# 6_DIG.net
KiCad netlist of a schematic drawn in Altium Designer
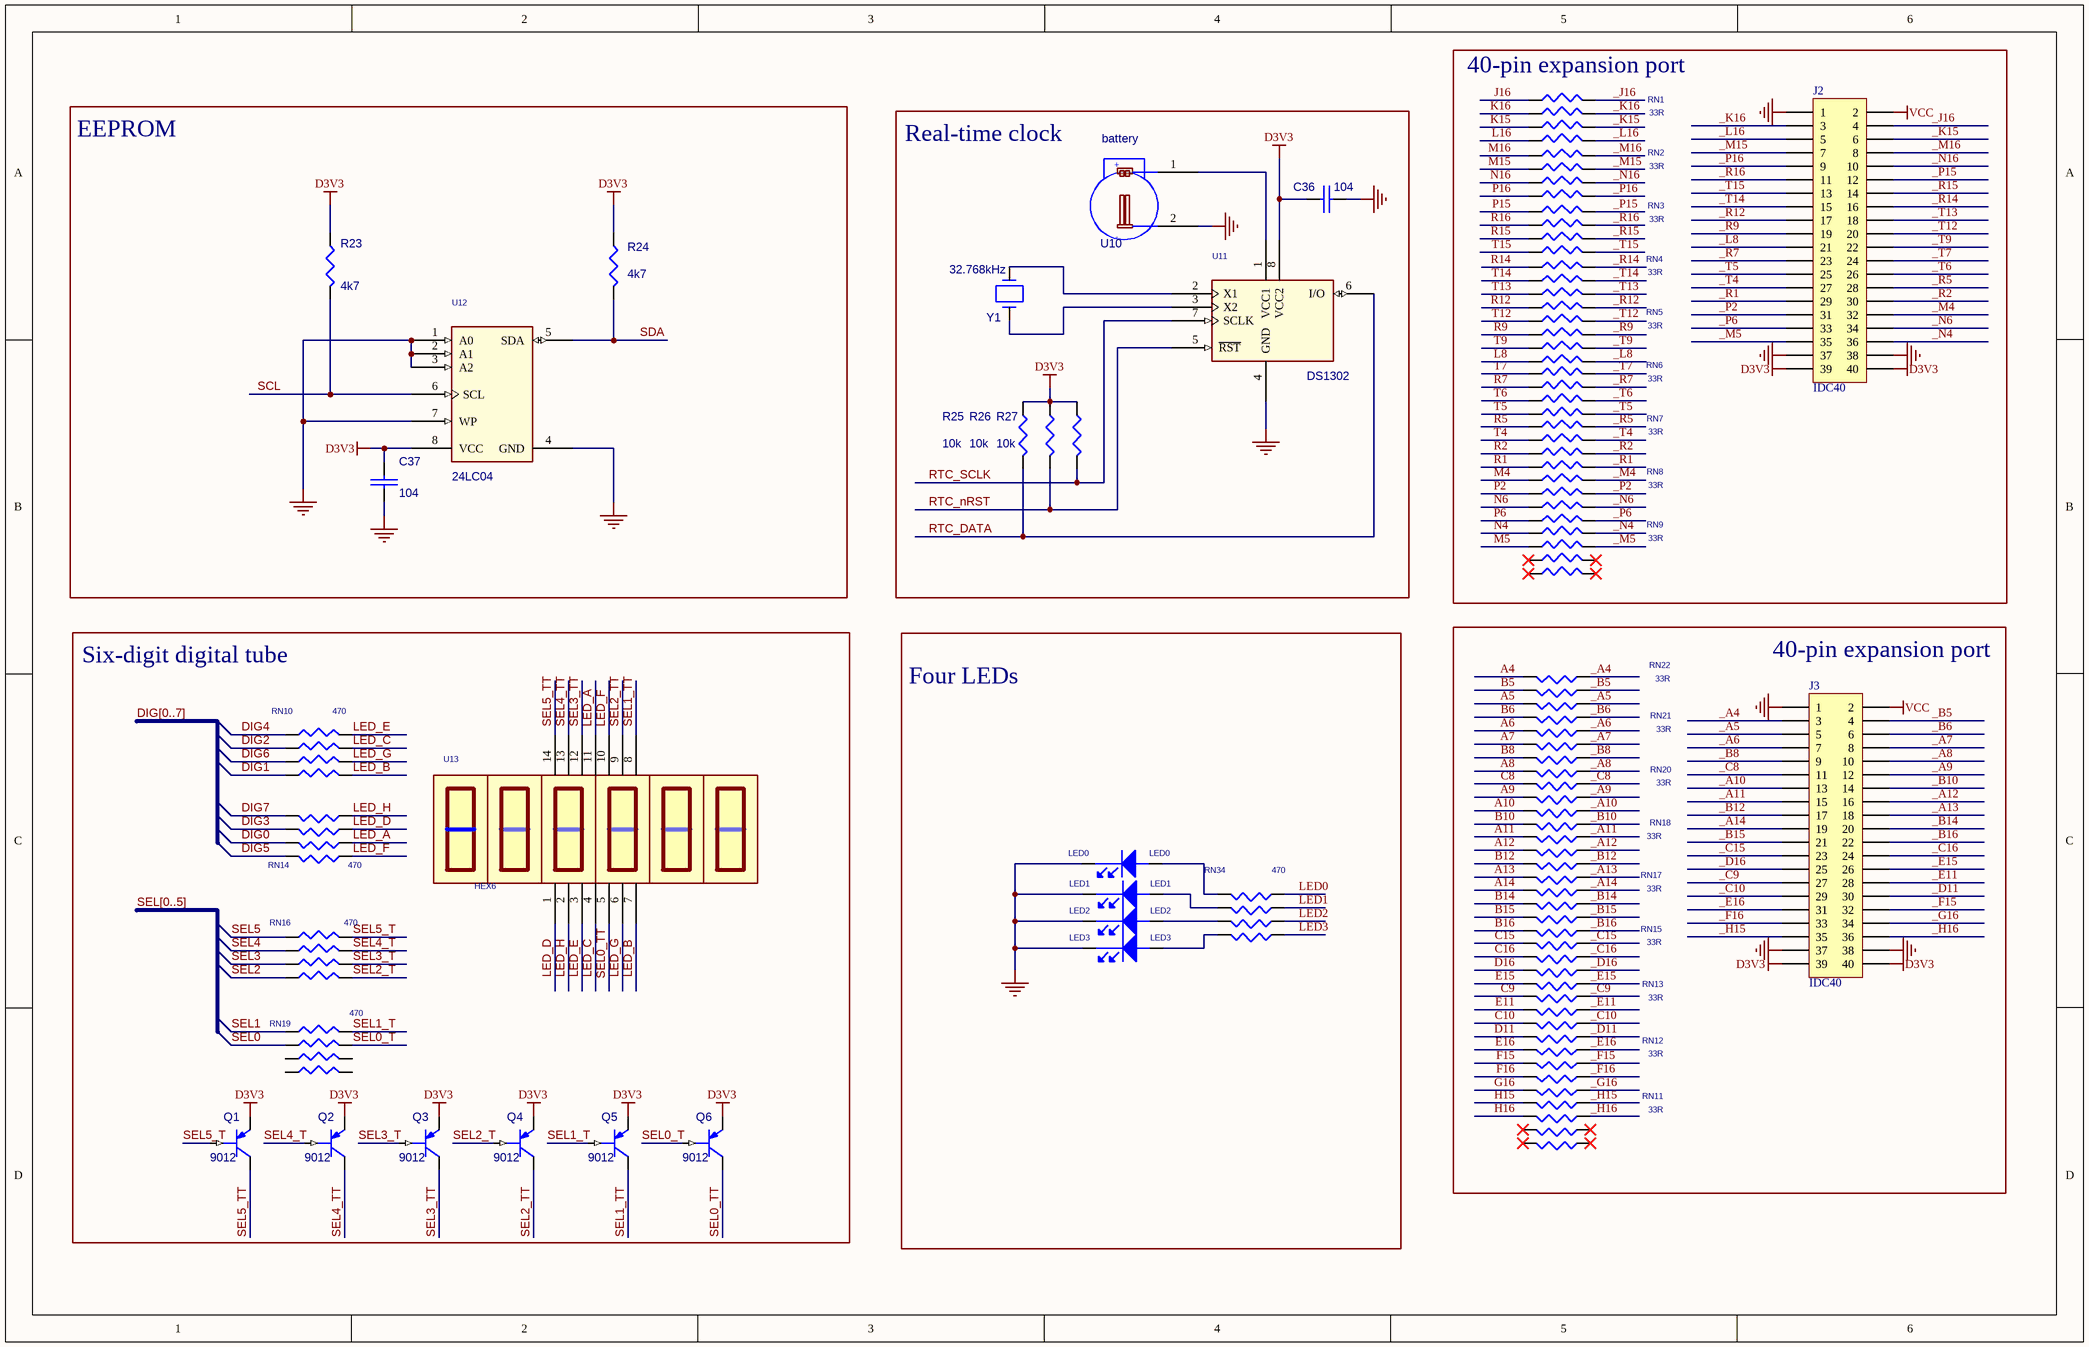
[diagram p0: 6_DIG.SchDoc]

(export (version "E")
  (design (tool "Eeschema 10.0.6"))
  (components
    (comp (ref "C36") (value "104") (footprint "0402") (libsource (lib "*") (part "C_Dup3")))
    (comp (ref "C37") (value "104") (footprint "0402") (libsource (lib "*") (part "C_Dup4")))
    (comp (ref "J2")
      (value "IDC40")
      (footprint "IDC-40J")
      (description "Header, 20-Pin, Dual row")
      (fields (field (name "PUBLISHER") "Altium Limited"))
      (libsource (lib "Miscellaneous Connectors") (part "MHDR2X20"))
    )
    (comp (ref "J3")
      (value "IDC40")
      (footprint "IDC-40J")
      (description "Header, 20-Pin, Dual row")
      (fields (field (name "PUBLISHER") "Altium Limited"))
      (libsource (lib "Miscellaneous Connectors") (part "MHDR2X20"))
    )
    (comp (ref "LED0") (value "LED0") (footprint "LEDSO") (libsource (lib "*") (part "LED_Dup1")))
    (comp (ref "LED1") (value "LED1") (footprint "LEDso") (libsource (lib "*") (part "LED_Dup1")))
    (comp (ref "LED2") (value "LED2") (footprint "LEDSO") (libsource (lib "*") (part "LED_Dup1")))
    (comp (ref "LED3") (value "LED3") (footprint "LEDSO") (libsource (lib "*") (part "LED_Dup1")))
    (comp (ref "Q1") (value "9012") (footprint "SOT23") (libsource (lib "*") (part "PNP")))
    (comp (ref "Q2") (value "9012") (footprint "SOT23") (libsource (lib "*") (part "PNP")))
    (comp (ref "Q3") (value "9012") (footprint "SOT23") (libsource (lib "*") (part "PNP")))
    (comp (ref "Q4") (value "9012") (footprint "SOT23") (libsource (lib "*") (part "PNP")))
    (comp (ref "Q5") (value "9012") (footprint "SOT23") (libsource (lib "*") (part "PNP")))
    (comp (ref "Q6") (value "9012") (footprint "SOT23") (libsource (lib "*") (part "PNP")))
    (comp (ref "R23") (value "4k7") (footprint "0603") (libsource (lib "*") (part "R_Dup6")))
    (comp (ref "R24") (value "4k7") (footprint "0603") (libsource (lib "*") (part "R_Dup6")))
    (comp (ref "R25") (value "10k") (footprint "0603") (libsource (lib "*") (part "R_Dup5")))
    (comp (ref "R26") (value "10k") (footprint "0603") (libsource (lib "*") (part "R_Dup5")))
    (comp (ref "R27") (value "10k") (footprint "0603") (libsource (lib "*") (part "R_Dup5")))
    (comp (ref "RN1") (value "33R") (footprint "RN-8P") (libsource (lib "*") (part "RN_Dup1")))
    (comp (ref "RN2") (value "33R") (footprint "RN-8P") (libsource (lib "*") (part "RN_Dup1")))
    (comp (ref "RN3") (value "33R") (footprint "RN-8P") (libsource (lib "*") (part "RN_Dup1")))
    (comp (ref "RN4") (value "33R") (footprint "RN-8P") (libsource (lib "*") (part "RN_Dup1")))
    (comp (ref "RN5") (value "33R") (footprint "RN-8P") (libsource (lib "*") (part "RN_Dup1")))
    (comp (ref "RN6") (value "33R") (footprint "RN-8P") (libsource (lib "*") (part "RN_Dup1")))
    (comp (ref "RN7") (value "33R") (footprint "RN-8P") (libsource (lib "*") (part "RN_Dup1")))
    (comp (ref "RN8") (value "33R") (footprint "RN-8P") (libsource (lib "*") (part "RN_Dup1")))
    (comp (ref "RN9") (value "33R") (footprint "RN-8P") (libsource (lib "*") (part "RN_Dup1")))
    (comp (ref "RN10") (value "470") (footprint "RN-8P") (libsource (lib "*") (part "RN")))
    (comp (ref "RN11") (value "33R") (footprint "RN-8P") (libsource (lib "*") (part "RN_Dup1")))
    (comp (ref "RN12") (value "33R") (footprint "RN-8P") (libsource (lib "*") (part "RN_Dup1")))
    (comp (ref "RN13") (value "33R") (footprint "RN-8P") (libsource (lib "*") (part "RN_Dup1")))
    (comp (ref "RN14") (value "470") (footprint "RN-8P") (libsource (lib "*") (part "RN")))
    (comp (ref "RN15") (value "33R") (footprint "RN-8P") (libsource (lib "*") (part "RN_Dup1")))
    (comp (ref "RN16") (value "470") (footprint "RN-8P") (libsource (lib "*") (part "RN")))
    (comp (ref "RN17") (value "33R") (footprint "RN-8P") (libsource (lib "*") (part "RN_Dup1")))
    (comp (ref "RN18") (value "33R") (footprint "RN-8P") (libsource (lib "*") (part "RN_Dup1")))
    (comp (ref "RN19") (value "470") (footprint "RN-8P") (libsource (lib "*") (part "RN")))
    (comp (ref "RN20") (value "33R") (footprint "RN-8P") (libsource (lib "*") (part "RN_Dup1")))
    (comp (ref "RN21") (value "33R") (footprint "RN-8P") (libsource (lib "*") (part "RN_Dup1")))
    (comp (ref "RN22") (value "33R") (footprint "RN-8P") (libsource (lib "*") (part "RN_Dup1")))
    (comp (ref "RN34") (value "470") (footprint "RN-8P") (libsource (lib "*") (part "RN")))
    (comp (ref "U10") (value "battery") (footprint "BATSO") (libsource (lib "*") (part "battery")))
    (comp (ref "U11")
      (value "DS1302")
      (fields (field (name "PART NUMBER") "TMP-13") (field (name "ICA_PARTNUM") "$$2098133$$DS1302S"))
      (libsource (lib "*") (part "DS1302_8SO"))
    )
    (comp (ref "U12") (value "24LC04") (libsource (lib "*") (part "24LC04B_0")))
    (comp (ref "U13") (value "HEX6") (libsource (lib "*") (part "HEX6")))
    (comp (ref "Y1") (value "32.768kHz") (libsource (lib "*") (part "ZTA")))
  )
  (nets
    (net (code "1") (name "/A4") (class "Default")
      (node (ref "RN22") (pin "5") (pinfunction "5_5") (pintype "passive"))
    )
    (net (code "2") (name "/A5") (class "Default")
      (node (ref "RN22") (pin "7") (pinfunction "7_7") (pintype "passive"))
    )
    (net (code "3") (name "/A6") (class "Default")
      (node (ref "RN21") (pin "5") (pinfunction "5_5") (pintype "passive"))
    )
    (net (code "4") (name "/A7") (class "Default")
      (node (ref "RN21") (pin "6") (pinfunction "6_6") (pintype "passive"))
    )
    (net (code "5") (name "/A8") (class "Default")
      (node (ref "RN21") (pin "8") (pinfunction "8_8") (pintype "passive"))
    )
    (net (code "6") (name "/A9") (class "Default")
      (node (ref "RN20") (pin "6") (pinfunction "6_6") (pintype "passive"))
    )
    (net (code "7") (name "/A10") (class "Default")
      (node (ref "RN20") (pin "7") (pinfunction "7_7") (pintype "passive"))
    )
    (net (code "8") (name "/A11") (class "Default")
      (node (ref "RN18") (pin "5") (pinfunction "5_5") (pintype "passive"))
    )
    (net (code "9") (name "/A12") (class "Default")
      (node (ref "RN18") (pin "6") (pinfunction "6_6") (pintype "passive"))
    )
    (net (code "10") (name "/A13") (class "Default")
      (node (ref "RN18") (pin "8") (pinfunction "8_8") (pintype "passive"))
    )
    (net (code "11") (name "/A14") (class "Default")
      (node (ref "RN17") (pin "5") (pinfunction "5_5") (pintype "passive"))
    )
    (net (code "12") (name "/B5") (class "Default")
      (node (ref "RN22") (pin "6") (pinfunction "6_6") (pintype "passive"))
    )
    (net (code "13") (name "/B6") (class "Default")
      (node (ref "RN22") (pin "8") (pinfunction "8_8") (pintype "passive"))
    )
    (net (code "14") (name "/B8") (class "Default")
      (node (ref "RN21") (pin "7") (pinfunction "7_7") (pintype "passive"))
    )
    (net (code "15") (name "/B10") (class "Default")
      (node (ref "RN20") (pin "8") (pinfunction "8_8") (pintype "passive"))
    )
    (net (code "16") (name "/B12") (class "Default")
      (node (ref "RN18") (pin "7") (pinfunction "7_7") (pintype "passive"))
    )
    (net (code "17") (name "/B14") (class "Default")
      (node (ref "RN17") (pin "6") (pinfunction "6_6") (pintype "passive"))
    )
    (net (code "18") (name "/B15") (class "Default")
      (node (ref "RN17") (pin "7") (pinfunction "7_7") (pintype "passive"))
    )
    (net (code "19") (name "/B16") (class "Default")
      (node (ref "RN17") (pin "8") (pinfunction "8_8") (pintype "passive"))
    )
    (net (code "20") (name "/C8") (class "Default")
      (node (ref "RN20") (pin "5") (pinfunction "5_5") (pintype "passive"))
    )
    (net (code "21") (name "/C9") (class "Default")
      (node (ref "RN13") (pin "5") (pinfunction "5_5") (pintype "passive"))
    )
    (net (code "22") (name "/C10") (class "Default")
      (node (ref "RN13") (pin "7") (pinfunction "7_7") (pintype "passive"))
    )
    (net (code "23") (name "/C15") (class "Default")
      (node (ref "RN15") (pin "5") (pinfunction "5_5") (pintype "passive"))
    )
    (net (code "24") (name "/C16") (class "Default")
      (node (ref "RN15") (pin "6") (pinfunction "6_6") (pintype "passive"))
    )
    (net (code "25") (name "/D11") (class "Default")
      (node (ref "RN13") (pin "8") (pinfunction "8_8") (pintype "passive"))
    )
    (net (code "26") (name "/D16") (class "Default")
      (node (ref "RN15") (pin "7") (pinfunction "7_7") (pintype "passive"))
    )
    (net (code "27") (name "/DIG0") (class "Default")
      (node (ref "RN14") (pin "7") (pinfunction "7_7") (pintype "passive"))
    )
    (net (code "28") (name "/DIG1") (class "Default")
      (node (ref "RN10") (pin "5") (pinfunction "5_5") (pintype "passive"))
    )
    (net (code "29") (name "/DIG2") (class "Default")
      (node (ref "RN10") (pin "7") (pinfunction "7_7") (pintype "passive"))
    )
    (net (code "30") (name "/DIG3") (class "Default")
      (node (ref "RN14") (pin "6") (pinfunction "6_6") (pintype "passive"))
    )
    (net (code "31") (name "/DIG4") (class "Default")
      (node (ref "RN10") (pin "8") (pinfunction "8_8") (pintype "passive"))
    )
    (net (code "32") (name "/DIG5") (class "Default")
      (node (ref "RN14") (pin "8") (pinfunction "8_8") (pintype "passive"))
    )
    (net (code "33") (name "/DIG6") (class "Default")
      (node (ref "RN10") (pin "6") (pinfunction "6_6") (pintype "passive"))
    )
    (net (code "34") (name "/DIG7") (class "Default")
      (node (ref "RN14") (pin "5") (pinfunction "5_5") (pintype "passive"))
    )
    (net (code "36") (name "/E11") (class "Default")
      (node (ref "RN13") (pin "6") (pinfunction "6_6") (pintype "passive"))
    )
    (net (code "37") (name "/E15") (class "Default")
      (node (ref "RN15") (pin "8") (pinfunction "8_8") (pintype "passive"))
    )
    (net (code "38") (name "/E16") (class "Default")
      (node (ref "RN12") (pin "5") (pinfunction "5_5") (pintype "passive"))
    )
    (net (code "39") (name "/F15") (class "Default")
      (node (ref "RN12") (pin "6") (pinfunction "6_6") (pintype "passive"))
    )
    (net (code "40") (name "/F16") (class "Default")
      (node (ref "RN12") (pin "7") (pinfunction "7_7") (pintype "passive"))
    )
    (net (code "41") (name "/G16") (class "Default")
      (node (ref "RN12") (pin "8") (pinfunction "8_8") (pintype "passive"))
    )
    (net (code "42") (name "/H15") (class "Default")
      (node (ref "RN11") (pin "5") (pinfunction "5_5") (pintype "passive"))
    )
    (net (code "43") (name "/H16") (class "Default")
      (node (ref "RN11") (pin "6") (pinfunction "6_6") (pintype "passive"))
    )
    (net (code "44") (name "/J16") (class "Default")
      (node (ref "RN1") (pin "1") (pinfunction "1_1") (pintype "passive"))
    )
    (net (code "45") (name "/K15") (class "Default")
      (node (ref "RN1") (pin "3") (pinfunction "3_3") (pintype "passive"))
    )
    (net (code "46") (name "/K16") (class "Default")
      (node (ref "RN1") (pin "2") (pinfunction "2_2") (pintype "passive"))
    )
    (net (code "47") (name "/L8") (class "Default")
      (node (ref "RN5") (pin "4") (pinfunction "4_4") (pintype "passive"))
    )
    (net (code "48") (name "/L16") (class "Default")
      (node (ref "RN1") (pin "4") (pinfunction "4_4") (pintype "passive"))
    )
    (net (code "49") (name "/LED0") (class "Default")
      (node (ref "RN34") (pin "4") (pinfunction "4_4") (pintype "passive"))
    )
    (net (code "50") (name "/LED1") (class "Default")
      (node (ref "RN34") (pin "3") (pinfunction "3_3") (pintype "passive"))
    )
    (net (code "51") (name "/LED2") (class "Default")
      (node (ref "RN34") (pin "2") (pinfunction "2_2") (pintype "passive"))
    )
    (net (code "52") (name "/LED3") (class "Default")
      (node (ref "RN34") (pin "1") (pinfunction "1_1") (pintype "passive"))
    )
    (net (code "53") (name "/LED_A") (class "Default")
      (node (ref "RN14") (pin "2") (pinfunction "2_2") (pintype "passive"))
      (node (ref "U13") (pin "11") (pinfunction "11_11") (pintype "passive"))
    )
    (net (code "54") (name "/LED_B") (class "Default")
      (node (ref "RN10") (pin "4") (pinfunction "4_4") (pintype "passive"))
      (node (ref "U13") (pin "7") (pinfunction "7_7") (pintype "passive"))
    )
    (net (code "55") (name "/LED_C") (class "Default")
      (node (ref "RN10") (pin "2") (pinfunction "2_2") (pintype "passive"))
      (node (ref "U13") (pin "4") (pinfunction "4_4") (pintype "passive"))
    )
    (net (code "56") (name "/LED_D") (class "Default")
      (node (ref "RN14") (pin "3") (pinfunction "3_3") (pintype "passive"))
      (node (ref "U13") (pin "1") (pinfunction "1_1") (pintype "passive"))
    )
    (net (code "57") (name "/LED_E") (class "Default")
      (node (ref "RN10") (pin "1") (pinfunction "1_1") (pintype "passive"))
      (node (ref "U13") (pin "3") (pinfunction "3_3") (pintype "passive"))
    )
    (net (code "58") (name "/LED_F") (class "Default")
      (node (ref "RN14") (pin "1") (pinfunction "1_1") (pintype "passive"))
      (node (ref "U13") (pin "10") (pinfunction "10_10") (pintype "passive"))
    )
    (net (code "59") (name "/LED_G") (class "Default")
      (node (ref "RN10") (pin "3") (pinfunction "3_3") (pintype "passive"))
      (node (ref "U13") (pin "6") (pinfunction "6_6") (pintype "passive"))
    )
    (net (code "60") (name "/LED_H") (class "Default")
      (node (ref "RN14") (pin "4") (pinfunction "4_4") (pintype "passive"))
      (node (ref "U13") (pin "2") (pinfunction "2_2") (pintype "passive"))
    )
    (net (code "61") (name "/M4") (class "Default")
      (node (ref "RN8") (pin "1") (pinfunction "1_1") (pintype "passive"))
    )
    (net (code "62") (name "/M5") (class "Default")
      (node (ref "RN9") (pin "2") (pinfunction "2_2") (pintype "passive"))
    )
    (net (code "63") (name "/M15") (class "Default")
      (node (ref "RN2") (pin "2") (pinfunction "2_2") (pintype "passive"))
    )
    (net (code "64") (name "/M16") (class "Default")
      (node (ref "RN2") (pin "1") (pinfunction "1_1") (pintype "passive"))
    )
    (net (code "65") (name "/N4") (class "Default")
      (node (ref "RN9") (pin "1") (pinfunction "1_1") (pintype "passive"))
    )
    (net (code "66") (name "/N6") (class "Default")
      (node (ref "RN8") (pin "3") (pinfunction "3_3") (pintype "passive"))
    )
    (net (code "67") (name "/N16") (class "Default")
      (node (ref "RN2") (pin "3") (pinfunction "3_3") (pintype "passive"))
    )
    (net (code "68") (name "/P2") (class "Default")
      (node (ref "RN8") (pin "2") (pinfunction "2_2") (pintype "passive"))
    )
    (net (code "69") (name "/P6") (class "Default")
      (node (ref "RN8") (pin "4") (pinfunction "4_4") (pintype "passive"))
    )
    (net (code "70") (name "/P15") (class "Default")
      (node (ref "RN3") (pin "1") (pinfunction "1_1") (pintype "passive"))
    )
    (net (code "71") (name "/P16") (class "Default")
      (node (ref "RN2") (pin "4") (pinfunction "4_4") (pintype "passive"))
    )
    (net (code "72") (name "/R1") (class "Default")
      (node (ref "RN7") (pin "4") (pinfunction "4_4") (pintype "passive"))
    )
    (net (code "73") (name "/R2") (class "Default")
      (node (ref "RN7") (pin "3") (pinfunction "3_3") (pintype "passive"))
    )
    (net (code "74") (name "/R5") (class "Default")
      (node (ref "RN7") (pin "1") (pinfunction "1_1") (pintype "passive"))
    )
    (net (code "75") (name "/R7") (class "Default")
      (node (ref "RN6") (pin "2") (pinfunction "2_2") (pintype "passive"))
    )
    (net (code "76") (name "/R9") (class "Default")
      (node (ref "RN5") (pin "2") (pinfunction "2_2") (pintype "passive"))
    )
    (net (code "77") (name "/R12") (class "Default")
      (node (ref "RN4") (pin "4") (pinfunction "4_4") (pintype "passive"))
    )
    (net (code "78") (name "/R14") (class "Default")
      (node (ref "RN4") (pin "1") (pinfunction "1_1") (pintype "passive"))
    )
    (net (code "79") (name "/R15") (class "Default")
      (node (ref "RN3") (pin "3") (pinfunction "3_3") (pintype "passive"))
    )
    (net (code "80") (name "/R16") (class "Default")
      (node (ref "RN3") (pin "2") (pinfunction "2_2") (pintype "passive"))
    )
    (net (code "81") (name "/RTC_DATA") (class "Default")
      (node (ref "R25") (pin "2") (pinfunction "2_2") (pintype "passive"))
      (node (ref "U11") (pin "6") (pinfunction "I/O_6") (pintype "bidirectional"))
    )
    (net (code "82") (name "/RTC_SCLK") (class "Default")
      (node (ref "R27") (pin "2") (pinfunction "2_2") (pintype "passive"))
      (node (ref "U11") (pin "7") (pinfunction "SCLK_7") (pintype "input"))
    )
    (net (code "83") (name "/RTC_nRST") (class "Default")
      (node (ref "R26") (pin "2") (pinfunction "2_2") (pintype "passive"))
      (node (ref "U11") (pin "5") (pinfunction "~{RST}_5") (pintype "input"))
    )
    (net (code "84") (name "/SCL") (class "Default")
      (node (ref "R23") (pin "2") (pinfunction "2_2") (pintype "passive"))
      (node (ref "U12") (pin "6") (pinfunction "SCL_6") (pintype "input"))
    )
    (net (code "85") (name "/SDA") (class "Default")
      (node (ref "R24") (pin "2") (pinfunction "2_2") (pintype "passive"))
      (node (ref "U12") (pin "5") (pinfunction "SDA_5") (pintype "bidirectional"))
    )
    (net (code "86") (name "/SEL0") (class "Default")
      (node (ref "RN19") (pin "7") (pinfunction "7_7") (pintype "passive"))
    )
    (net (code "87") (name "/SEL0_T") (class "Default")
      (node (ref "Q6") (pin "1") (pinfunction "BASE_1") (pintype "input"))
      (node (ref "RN19") (pin "2") (pinfunction "2_2") (pintype "passive"))
    )
    (net (code "88") (name "/SEL0_TT") (class "Default")
      (node (ref "Q6") (pin "3") (pinfunction "COLLECTOR_3") (pintype "passive"))
      (node (ref "U13") (pin "5") (pinfunction "5_5") (pintype "passive"))
    )
    (net (code "89") (name "/SEL1") (class "Default")
      (node (ref "RN19") (pin "8") (pinfunction "8_8") (pintype "passive"))
    )
    (net (code "90") (name "/SEL1_T") (class "Default")
      (node (ref "Q5") (pin "1") (pinfunction "BASE_1") (pintype "input"))
      (node (ref "RN19") (pin "1") (pinfunction "1_1") (pintype "passive"))
    )
    (net (code "91") (name "/SEL1_TT") (class "Default")
      (node (ref "Q5") (pin "3") (pinfunction "COLLECTOR_3") (pintype "passive"))
      (node (ref "U13") (pin "8") (pinfunction "8_8") (pintype "passive"))
    )
    (net (code "92") (name "/SEL2") (class "Default")
      (node (ref "RN16") (pin "5") (pinfunction "5_5") (pintype "passive"))
    )
    (net (code "93") (name "/SEL2_T") (class "Default")
      (node (ref "Q4") (pin "1") (pinfunction "BASE_1") (pintype "input"))
      (node (ref "RN16") (pin "4") (pinfunction "4_4") (pintype "passive"))
    )
    (net (code "94") (name "/SEL2_TT") (class "Default")
      (node (ref "Q4") (pin "3") (pinfunction "COLLECTOR_3") (pintype "passive"))
      (node (ref "U13") (pin "9") (pinfunction "9_9") (pintype "passive"))
    )
    (net (code "95") (name "/SEL3") (class "Default")
      (node (ref "RN16") (pin "6") (pinfunction "6_6") (pintype "passive"))
    )
    (net (code "96") (name "/SEL3_T") (class "Default")
      (node (ref "Q3") (pin "1") (pinfunction "BASE_1") (pintype "input"))
      (node (ref "RN16") (pin "3") (pinfunction "3_3") (pintype "passive"))
    )
    (net (code "97") (name "/SEL3_TT") (class "Default")
      (node (ref "Q3") (pin "3") (pinfunction "COLLECTOR_3") (pintype "passive"))
      (node (ref "U13") (pin "12") (pinfunction "12_12") (pintype "passive"))
    )
    (net (code "98") (name "/SEL4") (class "Default")
      (node (ref "RN16") (pin "7") (pinfunction "7_7") (pintype "passive"))
    )
    (net (code "99") (name "/SEL4_T") (class "Default")
      (node (ref "Q2") (pin "1") (pinfunction "BASE_1") (pintype "input"))
      (node (ref "RN16") (pin "2") (pinfunction "2_2") (pintype "passive"))
    )
    (net (code "100") (name "/SEL4_TT") (class "Default")
      (node (ref "Q2") (pin "3") (pinfunction "COLLECTOR_3") (pintype "passive"))
      (node (ref "U13") (pin "13") (pinfunction "13_13") (pintype "passive"))
    )
    (net (code "101") (name "/SEL5") (class "Default")
      (node (ref "RN16") (pin "8") (pinfunction "8_8") (pintype "passive"))
    )
    (net (code "102") (name "/SEL5_T") (class "Default")
      (node (ref "Q1") (pin "1") (pinfunction "BASE_1") (pintype "input"))
      (node (ref "RN16") (pin "1") (pinfunction "1_1") (pintype "passive"))
    )
    (net (code "103") (name "/SEL5_TT") (class "Default")
      (node (ref "Q1") (pin "3") (pinfunction "COLLECTOR_3") (pintype "passive"))
      (node (ref "U13") (pin "14") (pinfunction "14_14") (pintype "passive"))
    )
    (net (code "105") (name "/T4") (class "Default")
      (node (ref "RN7") (pin "2") (pinfunction "2_2") (pintype "passive"))
    )
    (net (code "106") (name "/T5") (class "Default")
      (node (ref "RN6") (pin "4") (pinfunction "4_4") (pintype "passive"))
    )
    (net (code "107") (name "/T6") (class "Default")
      (node (ref "RN6") (pin "3") (pinfunction "3_3") (pintype "passive"))
    )
    (net (code "108") (name "/T7") (class "Default")
      (node (ref "RN6") (pin "1") (pinfunction "1_1") (pintype "passive"))
    )
    (net (code "109") (name "/T9") (class "Default")
      (node (ref "RN5") (pin "3") (pinfunction "3_3") (pintype "passive"))
    )
    (net (code "110") (name "/T12") (class "Default")
      (node (ref "RN5") (pin "1") (pinfunction "1_1") (pintype "passive"))
    )
    (net (code "111") (name "/T13") (class "Default")
      (node (ref "RN4") (pin "3") (pinfunction "3_3") (pintype "passive"))
    )
    (net (code "112") (name "/T14") (class "Default")
      (node (ref "RN4") (pin "2") (pinfunction "2_2") (pintype "passive"))
    )
    (net (code "113") (name "/T15") (class "Default")
      (node (ref "RN3") (pin "4") (pinfunction "4_4") (pintype "passive"))
    )
    (net (code "114") (name "/_A4") (class "Default")
      (node (ref "J3") (pin "3") (pinfunction "3_3") (pintype "passive"))
      (node (ref "RN22") (pin "4") (pinfunction "4_4") (pintype "passive"))
    )
    (net (code "115") (name "/_A5") (class "Default")
      (node (ref "J3") (pin "5") (pinfunction "5_5") (pintype "passive"))
      (node (ref "RN22") (pin "2") (pinfunction "2_2") (pintype "passive"))
    )
    (net (code "116") (name "/_A6") (class "Default")
      (node (ref "J3") (pin "7") (pinfunction "7_7") (pintype "passive"))
      (node (ref "RN21") (pin "4") (pinfunction "4_4") (pintype "passive"))
    )
    (net (code "117") (name "/_A7") (class "Default")
      (node (ref "J3") (pin "8") (pinfunction "8_8") (pintype "passive"))
      (node (ref "RN21") (pin "3") (pinfunction "3_3") (pintype "passive"))
    )
    (net (code "118") (name "/_A8") (class "Default")
      (node (ref "J3") (pin "10") (pinfunction "10_10") (pintype "passive"))
      (node (ref "RN21") (pin "1") (pinfunction "1_1") (pintype "passive"))
    )
    (net (code "119") (name "/_A9") (class "Default")
      (node (ref "J3") (pin "12") (pinfunction "12_12") (pintype "passive"))
      (node (ref "RN20") (pin "3") (pinfunction "3_3") (pintype "passive"))
    )
    (net (code "120") (name "/_A10") (class "Default")
      (node (ref "J3") (pin "13") (pinfunction "13_13") (pintype "passive"))
      (node (ref "RN20") (pin "2") (pinfunction "2_2") (pintype "passive"))
    )
    (net (code "121") (name "/_A11") (class "Default")
      (node (ref "J3") (pin "15") (pinfunction "15_15") (pintype "passive"))
      (node (ref "RN18") (pin "4") (pinfunction "4_4") (pintype "passive"))
    )
    (net (code "122") (name "/_A12") (class "Default")
      (node (ref "J3") (pin "16") (pinfunction "16_16") (pintype "passive"))
      (node (ref "RN18") (pin "3") (pinfunction "3_3") (pintype "passive"))
    )
    (net (code "123") (name "/_A13") (class "Default")
      (node (ref "J3") (pin "18") (pinfunction "18_18") (pintype "passive"))
      (node (ref "RN18") (pin "1") (pinfunction "1_1") (pintype "passive"))
    )
    (net (code "124") (name "/_A14") (class "Default")
      (node (ref "J3") (pin "19") (pinfunction "19_19") (pintype "passive"))
      (node (ref "RN17") (pin "4") (pinfunction "4_4") (pintype "passive"))
    )
    (net (code "125") (name "/_B5") (class "Default")
      (node (ref "J3") (pin "4") (pinfunction "4_4") (pintype "passive"))
      (node (ref "RN22") (pin "3") (pinfunction "3_3") (pintype "passive"))
    )
    (net (code "126") (name "/_B6") (class "Default")
      (node (ref "J3") (pin "6") (pinfunction "6_6") (pintype "passive"))
      (node (ref "RN22") (pin "1") (pinfunction "1_1") (pintype "passive"))
    )
    (net (code "127") (name "/_B8") (class "Default")
      (node (ref "J3") (pin "9") (pinfunction "9_9") (pintype "passive"))
      (node (ref "RN21") (pin "2") (pinfunction "2_2") (pintype "passive"))
    )
    (net (code "128") (name "/_B10") (class "Default")
      (node (ref "J3") (pin "14") (pinfunction "14_14") (pintype "passive"))
      (node (ref "RN20") (pin "1") (pinfunction "1_1") (pintype "passive"))
    )
    (net (code "129") (name "/_B12") (class "Default")
      (node (ref "J3") (pin "17") (pinfunction "17_17") (pintype "passive"))
      (node (ref "RN18") (pin "2") (pinfunction "2_2") (pintype "passive"))
    )
    (net (code "130") (name "/_B14") (class "Default")
      (node (ref "J3") (pin "20") (pinfunction "20_20") (pintype "passive"))
      (node (ref "RN17") (pin "3") (pinfunction "3_3") (pintype "passive"))
    )
    (net (code "131") (name "/_B15") (class "Default")
      (node (ref "J3") (pin "21") (pinfunction "21_21") (pintype "passive"))
      (node (ref "RN17") (pin "2") (pinfunction "2_2") (pintype "passive"))
    )
    (net (code "132") (name "/_B16") (class "Default")
      (node (ref "J3") (pin "22") (pinfunction "22_22") (pintype "passive"))
      (node (ref "RN17") (pin "1") (pinfunction "1_1") (pintype "passive"))
    )
    (net (code "133") (name "/_C8") (class "Default")
      (node (ref "J3") (pin "11") (pinfunction "11_11") (pintype "passive"))
      (node (ref "RN20") (pin "4") (pinfunction "4_4") (pintype "passive"))
    )
    (net (code "134") (name "/_C9") (class "Default")
      (node (ref "J3") (pin "27") (pinfunction "27_27") (pintype "passive"))
      (node (ref "RN13") (pin "4") (pinfunction "4_4") (pintype "passive"))
    )
    (net (code "135") (name "/_C10") (class "Default")
      (node (ref "J3") (pin "29") (pinfunction "29_29") (pintype "passive"))
      (node (ref "RN13") (pin "2") (pinfunction "2_2") (pintype "passive"))
    )
    (net (code "136") (name "/_C15") (class "Default")
      (node (ref "J3") (pin "23") (pinfunction "23_23") (pintype "passive"))
      (node (ref "RN15") (pin "4") (pinfunction "4_4") (pintype "passive"))
    )
    (net (code "137") (name "/_C16") (class "Default")
      (node (ref "J3") (pin "24") (pinfunction "24_24") (pintype "passive"))
      (node (ref "RN15") (pin "3") (pinfunction "3_3") (pintype "passive"))
    )
    (net (code "138") (name "/_D11") (class "Default")
      (node (ref "J3") (pin "30") (pinfunction "30_30") (pintype "passive"))
      (node (ref "RN13") (pin "1") (pinfunction "1_1") (pintype "passive"))
    )
    (net (code "139") (name "/_D16") (class "Default")
      (node (ref "J3") (pin "25") (pinfunction "25_25") (pintype "passive"))
      (node (ref "RN15") (pin "2") (pinfunction "2_2") (pintype "passive"))
    )
    (net (code "140") (name "/_E11") (class "Default")
      (node (ref "J3") (pin "28") (pinfunction "28_28") (pintype "passive"))
      (node (ref "RN13") (pin "3") (pinfunction "3_3") (pintype "passive"))
    )
    (net (code "141") (name "/_E15") (class "Default")
      (node (ref "J3") (pin "26") (pinfunction "26_26") (pintype "passive"))
      (node (ref "RN15") (pin "1") (pinfunction "1_1") (pintype "passive"))
    )
    (net (code "142") (name "/_E16") (class "Default")
      (node (ref "J3") (pin "31") (pinfunction "31_31") (pintype "passive"))
      (node (ref "RN12") (pin "4") (pinfunction "4_4") (pintype "passive"))
    )
    (net (code "143") (name "/_F15") (class "Default")
      (node (ref "J3") (pin "32") (pinfunction "32_32") (pintype "passive"))
      (node (ref "RN12") (pin "3") (pinfunction "3_3") (pintype "passive"))
    )
    (net (code "144") (name "/_F16") (class "Default")
      (node (ref "J3") (pin "33") (pinfunction "33_33") (pintype "passive"))
      (node (ref "RN12") (pin "2") (pinfunction "2_2") (pintype "passive"))
    )
    (net (code "145") (name "/_G16") (class "Default")
      (node (ref "J3") (pin "34") (pinfunction "34_34") (pintype "passive"))
      (node (ref "RN12") (pin "1") (pinfunction "1_1") (pintype "passive"))
    )
    (net (code "146") (name "/_H15") (class "Default")
      (node (ref "J3") (pin "35") (pinfunction "35_35") (pintype "passive"))
      (node (ref "RN11") (pin "4") (pinfunction "4_4") (pintype "passive"))
    )
    (net (code "147") (name "/_H16") (class "Default")
      (node (ref "J3") (pin "36") (pinfunction "36_36") (pintype "passive"))
      (node (ref "RN11") (pin "3") (pinfunction "3_3") (pintype "passive"))
    )
    (net (code "148") (name "/_J16") (class "Default")
      (node (ref "J2") (pin "4") (pinfunction "4_4") (pintype "passive"))
      (node (ref "RN1") (pin "8") (pinfunction "8_8") (pintype "passive"))
    )
    (net (code "149") (name "/_K15") (class "Default")
      (node (ref "J2") (pin "6") (pinfunction "6_6") (pintype "passive"))
      (node (ref "RN1") (pin "6") (pinfunction "6_6") (pintype "passive"))
    )
    (net (code "150") (name "/_K16") (class "Default")
      (node (ref "J2") (pin "3") (pinfunction "3_3") (pintype "passive"))
      (node (ref "RN1") (pin "7") (pinfunction "7_7") (pintype "passive"))
    )
    (net (code "151") (name "/_L8") (class "Default")
      (node (ref "J2") (pin "21") (pinfunction "21_21") (pintype "passive"))
      (node (ref "RN5") (pin "5") (pinfunction "5_5") (pintype "passive"))
    )
    (net (code "152") (name "/_L16") (class "Default")
      (node (ref "J2") (pin "5") (pinfunction "5_5") (pintype "passive"))
      (node (ref "RN1") (pin "5") (pinfunction "5_5") (pintype "passive"))
    )
    (net (code "153") (name "/_M4") (class "Default")
      (node (ref "J2") (pin "32") (pinfunction "32_32") (pintype "passive"))
      (node (ref "RN8") (pin "8") (pinfunction "8_8") (pintype "passive"))
    )
    (net (code "154") (name "/_M5") (class "Default")
      (node (ref "J2") (pin "35") (pinfunction "35_35") (pintype "passive"))
      (node (ref "RN9") (pin "7") (pinfunction "7_7") (pintype "passive"))
    )
    (net (code "155") (name "/_M15") (class "Default")
      (node (ref "J2") (pin "7") (pinfunction "7_7") (pintype "passive"))
      (node (ref "RN2") (pin "7") (pinfunction "7_7") (pintype "passive"))
    )
    (net (code "156") (name "/_M16") (class "Default")
      (node (ref "J2") (pin "8") (pinfunction "8_8") (pintype "passive"))
      (node (ref "RN2") (pin "8") (pinfunction "8_8") (pintype "passive"))
    )
    (net (code "157") (name "/_N4") (class "Default")
      (node (ref "J2") (pin "36") (pinfunction "36_36") (pintype "passive"))
      (node (ref "RN9") (pin "8") (pinfunction "8_8") (pintype "passive"))
    )
    (net (code "158") (name "/_N6") (class "Default")
      (node (ref "J2") (pin "34") (pinfunction "34_34") (pintype "passive"))
      (node (ref "RN8") (pin "6") (pinfunction "6_6") (pintype "passive"))
    )
    (net (code "159") (name "/_N16") (class "Default")
      (node (ref "J2") (pin "10") (pinfunction "10_10") (pintype "passive"))
      (node (ref "RN2") (pin "6") (pinfunction "6_6") (pintype "passive"))
    )
    (net (code "160") (name "/_P2") (class "Default")
      (node (ref "J2") (pin "31") (pinfunction "31_31") (pintype "passive"))
      (node (ref "RN8") (pin "7") (pinfunction "7_7") (pintype "passive"))
    )
    (net (code "161") (name "/_P6") (class "Default")
      (node (ref "J2") (pin "33") (pinfunction "33_33") (pintype "passive"))
      (node (ref "RN8") (pin "5") (pinfunction "5_5") (pintype "passive"))
    )
    (net (code "162") (name "/_P15") (class "Default")
      (node (ref "J2") (pin "12") (pinfunction "12_12") (pintype "passive"))
      (node (ref "RN3") (pin "8") (pinfunction "8_8") (pintype "passive"))
    )
    (net (code "163") (name "/_P16") (class "Default")
      (node (ref "J2") (pin "9") (pinfunction "9_9") (pintype "passive"))
      (node (ref "RN2") (pin "5") (pinfunction "5_5") (pintype "passive"))
    )
    (net (code "164") (name "/_R1") (class "Default")
      (node (ref "J2") (pin "29") (pinfunction "29_29") (pintype "passive"))
      (node (ref "RN7") (pin "5") (pinfunction "5_5") (pintype "passive"))
    )
    (net (code "165") (name "/_R2") (class "Default")
      (node (ref "J2") (pin "30") (pinfunction "30_30") (pintype "passive"))
      (node (ref "RN7") (pin "6") (pinfunction "6_6") (pintype "passive"))
    )
    (net (code "166") (name "/_R5") (class "Default")
      (node (ref "J2") (pin "28") (pinfunction "28_28") (pintype "passive"))
      (node (ref "RN7") (pin "8") (pinfunction "8_8") (pintype "passive"))
    )
    (net (code "167") (name "/_R7") (class "Default")
      (node (ref "J2") (pin "23") (pinfunction "23_23") (pintype "passive"))
      (node (ref "RN6") (pin "7") (pinfunction "7_7") (pintype "passive"))
    )
    (net (code "168") (name "/_R9") (class "Default")
      (node (ref "J2") (pin "19") (pinfunction "19_19") (pintype "passive"))
      (node (ref "RN5") (pin "7") (pinfunction "7_7") (pintype "passive"))
    )
    (net (code "169") (name "/_R12") (class "Default")
      (node (ref "J2") (pin "17") (pinfunction "17_17") (pintype "passive"))
      (node (ref "RN4") (pin "5") (pinfunction "5_5") (pintype "passive"))
    )
    (net (code "170") (name "/_R14") (class "Default")
      (node (ref "J2") (pin "16") (pinfunction "16_16") (pintype "passive"))
      (node (ref "RN4") (pin "8") (pinfunction "8_8") (pintype "passive"))
    )
    (net (code "171") (name "/_R15") (class "Default")
      (node (ref "J2") (pin "14") (pinfunction "14_14") (pintype "passive"))
      (node (ref "RN3") (pin "6") (pinfunction "6_6") (pintype "passive"))
    )
    (net (code "172") (name "/_R16") (class "Default")
      (node (ref "J2") (pin "11") (pinfunction "11_11") (pintype "passive"))
      (node (ref "RN3") (pin "7") (pinfunction "7_7") (pintype "passive"))
    )
    (net (code "173") (name "/_T4") (class "Default")
      (node (ref "J2") (pin "27") (pinfunction "27_27") (pintype "passive"))
      (node (ref "RN7") (pin "7") (pinfunction "7_7") (pintype "passive"))
    )
    (net (code "174") (name "/_T5") (class "Default")
      (node (ref "J2") (pin "25") (pinfunction "25_25") (pintype "passive"))
      (node (ref "RN6") (pin "5") (pinfunction "5_5") (pintype "passive"))
    )
    (net (code "175") (name "/_T6") (class "Default")
      (node (ref "J2") (pin "26") (pinfunction "26_26") (pintype "passive"))
      (node (ref "RN6") (pin "6") (pinfunction "6_6") (pintype "passive"))
    )
    (net (code "176") (name "/_T7") (class "Default")
      (node (ref "J2") (pin "24") (pinfunction "24_24") (pintype "passive"))
      (node (ref "RN6") (pin "8") (pinfunction "8_8") (pintype "passive"))
    )
    (net (code "177") (name "/_T9") (class "Default")
      (node (ref "J2") (pin "22") (pinfunction "22_22") (pintype "passive"))
      (node (ref "RN5") (pin "6") (pinfunction "6_6") (pintype "passive"))
    )
    (net (code "178") (name "/_T12") (class "Default")
      (node (ref "J2") (pin "20") (pinfunction "20_20") (pintype "passive"))
      (node (ref "RN5") (pin "8") (pinfunction "8_8") (pintype "passive"))
    )
    (net (code "179") (name "/_T13") (class "Default")
      (node (ref "J2") (pin "18") (pinfunction "18_18") (pintype "passive"))
      (node (ref "RN4") (pin "6") (pinfunction "6_6") (pintype "passive"))
    )
    (net (code "180") (name "/_T14") (class "Default")
      (node (ref "J2") (pin "15") (pinfunction "15_15") (pintype "passive"))
      (node (ref "RN4") (pin "7") (pinfunction "7_7") (pintype "passive"))
    )
    (net (code "181") (name "/_T15") (class "Default")
      (node (ref "J2") (pin "13") (pinfunction "13_13") (pintype "passive"))
      (node (ref "RN3") (pin "5") (pinfunction "5_5") (pintype "passive"))
    )
    (net (code "182") (name "D3V3") (class "Default")
      (node (ref "C36") (pin "1") (pinfunction "1_1") (pintype "passive"))
      (node (ref "C37") (pin "1") (pinfunction "1_1") (pintype "passive"))
      (node (ref "J2") (pin "39") (pinfunction "39_39") (pintype "passive"))
      (node (ref "J2") (pin "40") (pinfunction "40_40") (pintype "passive"))
      (node (ref "J3") (pin "39") (pinfunction "39_39") (pintype "passive"))
      (node (ref "J3") (pin "40") (pinfunction "40_40") (pintype "passive"))
      (node (ref "Q1") (pin "2") (pinfunction "EMITTER_2") (pintype "passive"))
      (node (ref "Q2") (pin "2") (pinfunction "EMITTER_2") (pintype "passive"))
      (node (ref "Q3") (pin "2") (pinfunction "EMITTER_2") (pintype "passive"))
      (node (ref "Q4") (pin "2") (pinfunction "EMITTER_2") (pintype "passive"))
      (node (ref "Q5") (pin "2") (pinfunction "EMITTER_2") (pintype "passive"))
      (node (ref "Q6") (pin "2") (pinfunction "EMITTER_2") (pintype "passive"))
      (node (ref "R23") (pin "1") (pinfunction "1_1") (pintype "passive"))
      (node (ref "R24") (pin "1") (pinfunction "1_1") (pintype "passive"))
      (node (ref "R25") (pin "1") (pinfunction "1_1") (pintype "passive"))
      (node (ref "R26") (pin "1") (pinfunction "1_1") (pintype "passive"))
      (node (ref "R27") (pin "1") (pinfunction "1_1") (pintype "passive"))
      (node (ref "U11") (pin "8") (pinfunction "VCC2_8") (pintype "power_in"))
      (node (ref "U12") (pin "8") (pinfunction "VCC_8") (pintype "power_in"))
    )
    (net (code "183") (name "GND") (class "Default")
      (node (ref "C36") (pin "2") (pinfunction "2_2") (pintype "passive"))
      (node (ref "C37") (pin "2") (pinfunction "2_2") (pintype "passive"))
      (node (ref "J2") (pin "1") (pinfunction "1_1") (pintype "passive"))
      (node (ref "J2") (pin "37") (pinfunction "37_37") (pintype "passive"))
      (node (ref "J2") (pin "38") (pinfunction "38_38") (pintype "passive"))
      (node (ref "J3") (pin "1") (pinfunction "1_1") (pintype "passive"))
      (node (ref "J3") (pin "37") (pinfunction "37_37") (pintype "passive"))
      (node (ref "J3") (pin "38") (pinfunction "38_38") (pintype "passive"))
      (node (ref "LED0") (pin "2") (pinfunction "CATHODE_2") (pintype "passive"))
      (node (ref "LED1") (pin "2") (pinfunction "CATHODE_2") (pintype "passive"))
      (node (ref "LED2") (pin "2") (pinfunction "CATHODE_2") (pintype "passive"))
      (node (ref "LED3") (pin "2") (pinfunction "CATHODE_2") (pintype "passive"))
      (node (ref "U10") (pin "2") (pinfunction "GND_2") (pintype "passive"))
      (node (ref "U11") (pin "4") (pinfunction "GND_4") (pintype "power_in"))
      (node (ref "U12") (pin "1") (pinfunction "A0_1") (pintype "input"))
      (node (ref "U12") (pin "2") (pinfunction "A1_2") (pintype "input"))
      (node (ref "U12") (pin "3") (pinfunction "A2_3") (pintype "input"))
      (node (ref "U12") (pin "4") (pinfunction "GND_4") (pintype "power_in"))
      (node (ref "U12") (pin "7") (pinfunction "WP_7") (pintype "input"))
    )
    (net (code "184") (name "Net-(LED0-ANODE)") (class "Default")
      (node (ref "LED0") (pin "1") (pinfunction "ANODE_1") (pintype "passive"))
      (node (ref "RN34") (pin "5") (pinfunction "5_5") (pintype "passive"))
    )
    (net (code "185") (name "Net-(LED1-ANODE)") (class "Default")
      (node (ref "LED1") (pin "1") (pinfunction "ANODE_1") (pintype "passive"))
      (node (ref "RN34") (pin "6") (pinfunction "6_6") (pintype "passive"))
    )
    (net (code "186") (name "Net-(LED2-ANODE)") (class "Default")
      (node (ref "LED2") (pin "1") (pinfunction "ANODE_1") (pintype "passive"))
      (node (ref "RN34") (pin "7") (pinfunction "7_7") (pintype "passive"))
    )
    (net (code "187") (name "Net-(LED3-ANODE)") (class "Default")
      (node (ref "LED3") (pin "1") (pinfunction "ANODE_1") (pintype "passive"))
      (node (ref "RN34") (pin "8") (pinfunction "8_8") (pintype "passive"))
    )
    (net (code "188") (name "Net-(U10-VBAT)") (class "Default")
      (node (ref "U10") (pin "1") (pinfunction "VBAT_1") (pintype "passive"))
      (node (ref "U11") (pin "1") (pinfunction "VCC1_1") (pintype "power_in"))
    )
    (net (code "189") (name "Net-(U11-X1)") (class "Default")
      (node (ref "U11") (pin "2") (pinfunction "X1_2") (pintype "passive"))
      (node (ref "Y1") (pin "1") (pinfunction "1_1") (pintype "passive"))
    )
    (net (code "190") (name "Net-(U11-X2)") (class "Default")
      (node (ref "U11") (pin "3") (pinfunction "X2_3") (pintype "passive"))
      (node (ref "Y1") (pin "2") (pinfunction "2_2") (pintype "passive"))
    )
    (net (code "191") (name "VCC") (class "Default")
      (node (ref "J2") (pin "2") (pinfunction "2_2") (pintype "passive"))
      (node (ref "J3") (pin "2") (pinfunction "2_2") (pintype "passive"))
    )
    (net (code "192") (name "unconnected-(RN9-Pad3)") (class "Default")
      (node (ref "RN9") (pin "3") (pinfunction "3_3") (pintype "passive+no_connect"))
    )
    (net (code "193") (name "unconnected-(RN9-Pad4)") (class "Default")
      (node (ref "RN9") (pin "4") (pinfunction "4_4") (pintype "passive+no_connect"))
    )
    (net (code "194") (name "unconnected-(RN9-Pad5)") (class "Default")
      (node (ref "RN9") (pin "5") (pinfunction "5_5") (pintype "passive+no_connect"))
    )
    (net (code "195") (name "unconnected-(RN9-Pad6)") (class "Default")
      (node (ref "RN9") (pin "6") (pinfunction "6_6") (pintype "passive+no_connect"))
    )
    (net (code "196") (name "unconnected-(RN11-Pad1)") (class "Default")
      (node (ref "RN11") (pin "1") (pinfunction "1_1") (pintype "passive+no_connect"))
    )
    (net (code "197") (name "unconnected-(RN11-Pad2)") (class "Default")
      (node (ref "RN11") (pin "2") (pinfunction "2_2") (pintype "passive+no_connect"))
    )
    (net (code "198") (name "unconnected-(RN11-Pad7)") (class "Default")
      (node (ref "RN11") (pin "7") (pinfunction "7_7") (pintype "passive+no_connect"))
    )
    (net (code "199") (name "unconnected-(RN11-Pad8)") (class "Default")
      (node (ref "RN11") (pin "8") (pinfunction "8_8") (pintype "passive+no_connect"))
    )
    (net (code "200") (name "unconnected-(RN19-Pad3)") (class "Default")
      (node (ref "RN19") (pin "3") (pinfunction "3_3") (pintype "passive"))
    )
    (net (code "201") (name "unconnected-(RN19-Pad4)") (class "Default")
      (node (ref "RN19") (pin "4") (pinfunction "4_4") (pintype "passive"))
    )
    (net (code "202") (name "unconnected-(RN19-Pad5)") (class "Default")
      (node (ref "RN19") (pin "5") (pinfunction "5_5") (pintype "passive"))
    )
    (net (code "203") (name "unconnected-(RN19-Pad6)") (class "Default")
      (node (ref "RN19") (pin "6") (pinfunction "6_6") (pintype "passive"))
    )
  )
)
